# vending_machine_V1_1.net
KiCad netlist of a schematic drawn in Altium Designer
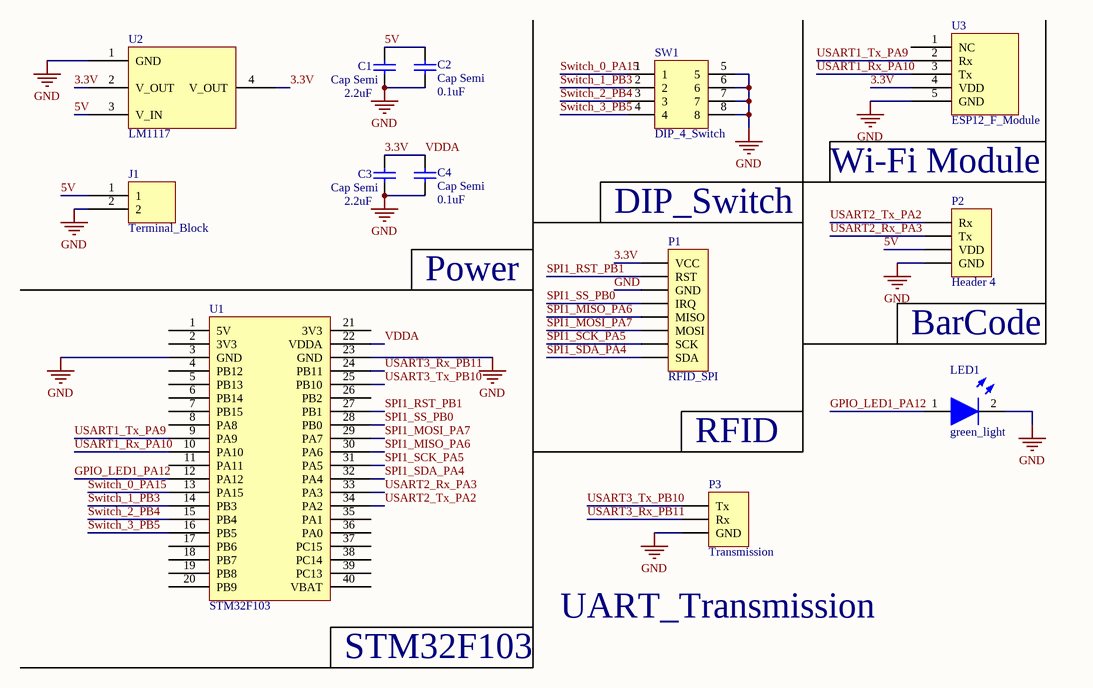
[diagram p0: vending_machine_V1.1.SchDoc]

(export (version "E")
  (design (tool "Eeschema 10.0.6"))
  (components
    (comp (ref "C1")
      (value "Cap Semi")
      (footprint "1608[0603]")
      (description "Capacitor (Semiconductor SIM Model)")
      (fields (field (name "ALTIUM_VALUE") "2.2uF") (field (name "PUBLISHER") "Altium Limited"))
      (libsource (lib "Miscellaneous Devices") (part "Cap Semi"))
    )
    (comp (ref "C2")
      (value "Cap Semi")
      (footprint "1608[0603]")
      (description "Capacitor (Semiconductor SIM Model)")
      (fields (field (name "ALTIUM_VALUE") "0.1uF") (field (name "PUBLISHER") "Altium Limited"))
      (libsource (lib "Miscellaneous Devices") (part "Cap Semi"))
    )
    (comp (ref "C3")
      (value "Cap Semi")
      (footprint "1608[0603]")
      (description "Capacitor (Semiconductor SIM Model)")
      (fields (field (name "ALTIUM_VALUE") "2.2uF") (field (name "PUBLISHER") "Altium Limited"))
      (libsource (lib "Miscellaneous Devices") (part "Cap Semi"))
    )
    (comp (ref "C4")
      (value "Cap Semi")
      (footprint "1608[0603]")
      (description "Capacitor (Semiconductor SIM Model)")
      (fields (field (name "ALTIUM_VALUE") "0.1uF") (field (name "PUBLISHER") "Altium Limited"))
      (libsource (lib "Miscellaneous Devices") (part "Cap Semi"))
    )
    (comp (ref "J1")
      (value "Terminal_Block")
      (footprint "terminal block")
      (libsource (lib "Lab_share") (part "Terminal Block"))
    )
    (comp (ref "LED1")
      (value "green_light")
      (footprint "LED_Green")
      (libsource (lib "Lab_share") (part "LED_Green"))
    )
    (comp (ref "P1")
      (value "RFID_SPI")
      (footprint "HDR1X8")
      (description "Header, 8-Pin")
      (fields (field (name "PUBLISHER") "Altium Limited"))
      (libsource (lib "Miscellaneous Connectors") (part "Header 8"))
    )
    (comp (ref "P2")
      (value "Header 4")
      (footprint "HDR1X4")
      (description "Header, 4-Pin")
      (fields (field (name "PUBLISHER") "Altium Limited"))
      (libsource (lib "Miscellaneous Connectors") (part "Header 4"))
    )
    (comp (ref "P3")
      (value "Transmission")
      (footprint "HDR1X3")
      (description "Header, 3-Pin")
      (fields (field (name "PUBLISHER") "Altium Limited"))
      (libsource (lib "Miscellaneous Connectors") (part "Header 3"))
    )
    (comp (ref "SW1")
      (value "DIP_4_Switch")
      (footprint "Switch_4")
      (libsource (lib "Lab_share") (part "Switch_4"))
    )
    (comp (ref "U1")
      (value "STM32F103")
      (footprint "STM32F103")
      (libsource (lib "Lab_share") (part "STM32F103"))
    )
    (comp (ref "U2")
      (value "LM1117")
      (footprint "LM1117 - duplicate")
      (libsource (lib "Lab_share") (part "LM1117"))
    )
    (comp (ref "U3")
      (value "ESP12_F_Module")
      (footprint "ESP12_F_Holtek")
      (libsource (lib "Lab_share") (part "ESP12_F_Holtek"))
    )
  )
  (nets
    (net (code "1") (name "/3.3V") (class "Default")
      (node (ref "C3") (pin "2") (pinfunction "2_2") (pintype "passive"))
      (node (ref "C4") (pin "2") (pinfunction "2_2") (pintype "passive"))
      (node (ref "P1") (pin "1") (pinfunction "VCC_1") (pintype "passive"))
      (node (ref "U1") (pin "22") (pinfunction "VDDA_22") (pintype "passive"))
      (node (ref "U2") (pin "2") (pinfunction "V_OUT_2") (pintype "passive"))
      (node (ref "U2") (pin "4") (pinfunction "V_OUT_4") (pintype "passive"))
      (node (ref "U3") (pin "4") (pinfunction "VDD_4") (pintype "passive"))
    )
    (net (code "2") (name "/5V") (class "Default")
      (node (ref "C1") (pin "2") (pinfunction "2_2") (pintype "passive"))
      (node (ref "C2") (pin "2") (pinfunction "2_2") (pintype "passive"))
      (node (ref "J1") (pin "1") (pinfunction "1_1") (pintype "passive"))
      (node (ref "P2") (pin "3") (pinfunction "VDD_3") (pintype "passive"))
      (node (ref "U2") (pin "3") (pinfunction "V_IN_3") (pintype "passive"))
    )
    (net (code "3") (name "/GPIO_LED1_PA12") (class "Default")
      (node (ref "LED1") (pin "1") (pintype "passive"))
      (node (ref "U1") (pin "12") (pinfunction "PA12_12") (pintype "passive"))
    )
    (net (code "4") (name "/SPI1_MISO_PA6") (class "Default")
      (node (ref "P1") (pin "5") (pinfunction "MISO_5") (pintype "passive"))
      (node (ref "U1") (pin "30") (pinfunction "PA6_30") (pintype "passive"))
    )
    (net (code "5") (name "/SPI1_MOSI_PA7") (class "Default")
      (node (ref "P1") (pin "6") (pinfunction "MOSI_6") (pintype "passive"))
      (node (ref "U1") (pin "29") (pinfunction "PA7_29") (pintype "passive"))
    )
    (net (code "6") (name "/SPI1_RST_PB1") (class "Default")
      (node (ref "P1") (pin "2") (pinfunction "RST_2") (pintype "passive"))
      (node (ref "U1") (pin "27") (pinfunction "PB1_27") (pintype "passive"))
    )
    (net (code "7") (name "/SPI1_SCK_PA5") (class "Default")
      (node (ref "P1") (pin "7") (pinfunction "SCK_7") (pintype "passive"))
      (node (ref "U1") (pin "31") (pinfunction "PA5_31") (pintype "passive"))
    )
    (net (code "8") (name "/SPI1_SDA_PA4") (class "Default")
      (node (ref "P1") (pin "8") (pinfunction "SDA_8") (pintype "passive"))
      (node (ref "U1") (pin "32") (pinfunction "PA4_32") (pintype "passive"))
    )
    (net (code "9") (name "/SPI1_SS_PB0") (class "Default")
      (node (ref "P1") (pin "4") (pinfunction "IRQ_4") (pintype "passive"))
      (node (ref "U1") (pin "28") (pinfunction "PB0_28") (pintype "passive"))
    )
    (net (code "10") (name "/Switch_0_PA15") (class "Default")
      (node (ref "SW1") (pin "1") (pinfunction "1_1") (pintype "passive"))
      (node (ref "U1") (pin "13") (pinfunction "PA15_13") (pintype "passive"))
    )
    (net (code "11") (name "/Switch_1_PB3") (class "Default")
      (node (ref "SW1") (pin "2") (pinfunction "2_2") (pintype "passive"))
      (node (ref "U1") (pin "14") (pinfunction "PB3_14") (pintype "passive"))
    )
    (net (code "12") (name "/Switch_2_PB4") (class "Default")
      (node (ref "SW1") (pin "3") (pinfunction "3_3") (pintype "passive"))
      (node (ref "U1") (pin "15") (pinfunction "PB4_15") (pintype "passive"))
    )
    (net (code "13") (name "/Switch_3_PB5") (class "Default")
      (node (ref "SW1") (pin "4") (pinfunction "4_4") (pintype "passive"))
      (node (ref "U1") (pin "16") (pinfunction "PB5_16") (pintype "passive"))
    )
    (net (code "14") (name "/USART1_Rx_PA10") (class "Default")
      (node (ref "U1") (pin "10") (pinfunction "PA10_10") (pintype "passive"))
      (node (ref "U3") (pin "3") (pinfunction "Tx_3") (pintype "passive"))
    )
    (net (code "15") (name "/USART1_Tx_PA9") (class "Default")
      (node (ref "U1") (pin "9") (pinfunction "PA9_9") (pintype "passive"))
      (node (ref "U3") (pin "2") (pinfunction "Rx_2") (pintype "passive"))
    )
    (net (code "16") (name "/USART2_Rx_PA3") (class "Default")
      (node (ref "P2") (pin "2") (pinfunction "Tx_2") (pintype "passive"))
      (node (ref "U1") (pin "33") (pinfunction "PA3_33") (pintype "passive"))
    )
    (net (code "17") (name "/USART2_Tx_PA2") (class "Default")
      (node (ref "P2") (pin "1") (pinfunction "Rx_1") (pintype "passive"))
      (node (ref "U1") (pin "34") (pinfunction "PA2_34") (pintype "passive"))
    )
    (net (code "18") (name "/USART3_Rx_PB11") (class "Default")
      (node (ref "P3") (pin "2") (pinfunction "Rx_2") (pintype "passive"))
      (node (ref "U1") (pin "24") (pinfunction "PB11_24") (pintype "passive"))
    )
    (net (code "19") (name "/USART3_Tx_PB10") (class "Default")
      (node (ref "P3") (pin "1") (pinfunction "Tx_1") (pintype "passive"))
      (node (ref "U1") (pin "25") (pinfunction "PB10_25") (pintype "passive"))
    )
    (net (code "20") (name "GND") (class "Default")
      (node (ref "C1") (pin "1") (pinfunction "1_1") (pintype "passive"))
      (node (ref "C2") (pin "1") (pinfunction "1_1") (pintype "passive"))
      (node (ref "C3") (pin "1") (pinfunction "1_1") (pintype "passive"))
      (node (ref "C4") (pin "1") (pinfunction "1_1") (pintype "passive"))
      (node (ref "J1") (pin "2") (pinfunction "2_2") (pintype "passive"))
      (node (ref "LED1") (pin "2") (pintype "passive"))
      (node (ref "P1") (pin "3") (pinfunction "GND_3") (pintype "passive"))
      (node (ref "P2") (pin "4") (pinfunction "GND_4") (pintype "passive"))
      (node (ref "P3") (pin "3") (pinfunction "GND_3") (pintype "passive"))
      (node (ref "SW1") (pin "5") (pinfunction "5_5") (pintype "passive"))
      (node (ref "SW1") (pin "6") (pinfunction "6_6") (pintype "passive"))
      (node (ref "SW1") (pin "7") (pinfunction "7_7") (pintype "passive"))
      (node (ref "SW1") (pin "8") (pinfunction "8_8") (pintype "passive"))
      (node (ref "U1") (pin "23") (pinfunction "GND_23") (pintype "passive"))
      (node (ref "U1") (pin "3") (pinfunction "GND_3") (pintype "passive"))
      (node (ref "U2") (pin "1") (pinfunction "GND_1") (pintype "passive"))
      (node (ref "U3") (pin "5") (pinfunction "GND_5") (pintype "passive"))
    )
    (net (code "21") (name "unconnected-(U1-3V3-Pad2)") (class "Default")
      (node (ref "U1") (pin "2") (pinfunction "3V3_2") (pintype "passive"))
    )
    (net (code "22") (name "unconnected-(U1-3V3-Pad21)") (class "Default")
      (node (ref "U1") (pin "21") (pinfunction "3V3_21") (pintype "passive"))
    )
    (net (code "23") (name "unconnected-(U1-5V-Pad1)") (class "Default")
      (node (ref "U1") (pin "1") (pinfunction "5V_1") (pintype "passive"))
    )
    (net (code "24") (name "unconnected-(U1-PA0-Pad36)") (class "Default")
      (node (ref "U1") (pin "36") (pinfunction "PA0_36") (pintype "passive"))
    )
    (net (code "25") (name "unconnected-(U1-PA1-Pad35)") (class "Default")
      (node (ref "U1") (pin "35") (pinfunction "PA1_35") (pintype "passive"))
    )
    (net (code "26") (name "unconnected-(U1-PA8-Pad8)") (class "Default")
      (node (ref "U1") (pin "8") (pinfunction "PA8_8") (pintype "passive"))
    )
    (net (code "27") (name "unconnected-(U1-PA11-Pad11)") (class "Default")
      (node (ref "U1") (pin "11") (pinfunction "PA11_11") (pintype "passive"))
    )
    (net (code "28") (name "unconnected-(U1-PB2-Pad26)") (class "Default")
      (node (ref "U1") (pin "26") (pinfunction "PB2_26") (pintype "passive"))
    )
    (net (code "29") (name "unconnected-(U1-PB6-Pad17)") (class "Default")
      (node (ref "U1") (pin "17") (pinfunction "PB6_17") (pintype "passive"))
    )
    (net (code "30") (name "unconnected-(U1-PB7-Pad18)") (class "Default")
      (node (ref "U1") (pin "18") (pinfunction "PB7_18") (pintype "passive"))
    )
    (net (code "31") (name "unconnected-(U1-PB8-Pad19)") (class "Default")
      (node (ref "U1") (pin "19") (pinfunction "PB8_19") (pintype "passive"))
    )
    (net (code "32") (name "unconnected-(U1-PB9-Pad20)") (class "Default")
      (node (ref "U1") (pin "20") (pinfunction "PB9_20") (pintype "passive"))
    )
    (net (code "33") (name "unconnected-(U1-PB12-Pad4)") (class "Default")
      (node (ref "U1") (pin "4") (pinfunction "PB12_4") (pintype "passive"))
    )
    (net (code "34") (name "unconnected-(U1-PB13-Pad5)") (class "Default")
      (node (ref "U1") (pin "5") (pinfunction "PB13_5") (pintype "passive"))
    )
    (net (code "35") (name "unconnected-(U1-PB14-Pad6)") (class "Default")
      (node (ref "U1") (pin "6") (pinfunction "PB14_6") (pintype "passive"))
    )
    (net (code "36") (name "unconnected-(U1-PB15-Pad7)") (class "Default")
      (node (ref "U1") (pin "7") (pinfunction "PB15_7") (pintype "passive"))
    )
    (net (code "37") (name "unconnected-(U1-PC13-Pad39)") (class "Default")
      (node (ref "U1") (pin "39") (pinfunction "PC13_39") (pintype "passive"))
    )
    (net (code "38") (name "unconnected-(U1-PC14-Pad38)") (class "Default")
      (node (ref "U1") (pin "38") (pinfunction "PC14_38") (pintype "passive"))
    )
    (net (code "39") (name "unconnected-(U1-PC15-Pad37)") (class "Default")
      (node (ref "U1") (pin "37") (pinfunction "PC15_37") (pintype "passive"))
    )
    (net (code "40") (name "unconnected-(U1-VBAT-Pad40)") (class "Default")
      (node (ref "U1") (pin "40") (pinfunction "VBAT_40") (pintype "passive"))
    )
    (net (code "41") (name "unconnected-(U3-NC-Pad1)") (class "Default")
      (node (ref "U3") (pin "1") (pinfunction "NC_1") (pintype "passive"))
    )
  )
)
